# CAMERAv1_4.net
KiCad netlist of a schematic drawn in Altium Designer
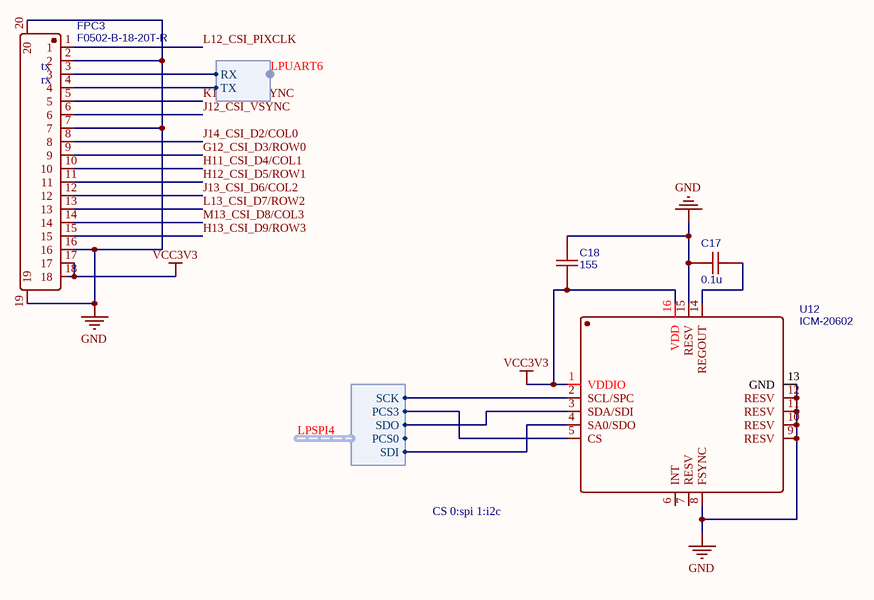
[diagram p0: CAMERAv1.4.SchDoc]

(export (version "E")
  (design (tool "Eeschema 10.0.6"))
  (components
    (comp (ref "C17")
      (value "0.1u")
      (footprint "C0603")
      (fields (field (name "CONTRIBUTOR") "LCEDA_Lib"))
      (libsource (lib "JLC") (part "C0603"))
    )
    (comp (ref "C18")
      (value "155")
      (footprint "C0603")
      (fields (field (name "CONTRIBUTOR") "LCEDA_Lib"))
      (libsource (lib "JLC") (part "C0603"))
    )
    (comp (ref "FPC3")
      (value "F0502-B-18-20T-R")
      (footprint "FPC-SMD_18P-P0.50_F0502-B-18-20T-R")
      (fields (field (name "BOM_SUPPLIER PART") "C512918") (field (name "CONTRIBUTOR") "LCSC"))
      (libsource (lib "JLC") (part "F0502-B-18-20T-R"))
    )
    (comp (ref "U12")
      (value "ICM-20602")
      (footprint "LGA-16_L3.0-W3.0-P0.50-BL")
      (fields (field (name "BOM_SUPPLIER PART") "C97633") (field (name "CONTRIBUTOR") "LCSC"))
      (libsource (lib "JLC") (part "ICM-20602"))
    )
  )
  (nets
    (net (code "2") (name "/G12_CSI_D3{slash}ROW0") (class "Default")
      (node (ref "FPC3") (pin "9") (pinfunction "9_9") (pintype "passive"))
    )
    (net (code "3") (name "/H11_CSI_D4{slash}COL1") (class "Default")
      (node (ref "FPC3") (pin "10") (pinfunction "10_10") (pintype "passive"))
    )
    (net (code "4") (name "/H12_CSI_D5{slash}ROW1") (class "Default")
      (node (ref "FPC3") (pin "11") (pinfunction "11_11") (pintype "passive"))
    )
    (net (code "5") (name "/H13_CSI_D9{slash}ROW3") (class "Default")
      (node (ref "FPC3") (pin "15") (pinfunction "15_15") (pintype "passive"))
    )
    (net (code "6") (name "/J12_CSI_VSYNC") (class "Default")
      (node (ref "FPC3") (pin "6") (pinfunction "6_6") (pintype "passive"))
    )
    (net (code "7") (name "/J13_CSI_D6{slash}COL2") (class "Default")
      (node (ref "FPC3") (pin "12") (pinfunction "12_12") (pintype "passive"))
    )
    (net (code "8") (name "/J14_CSI_D2{slash}COL0") (class "Default")
      (node (ref "FPC3") (pin "8") (pinfunction "8_8") (pintype "passive"))
    )
    (net (code "9") (name "/K10_CSI_HSYNC") (class "Default")
      (node (ref "FPC3") (pin "5") (pinfunction "5_5") (pintype "passive"))
    )
    (net (code "10") (name "/L12_CSI_PIXCLK") (class "Default")
      (node (ref "FPC3") (pin "1") (pinfunction "1_1") (pintype "passive"))
    )
    (net (code "11") (name "/L13_CSI_D7{slash}ROW2") (class "Default")
      (node (ref "FPC3") (pin "13") (pinfunction "13_13") (pintype "passive"))
    )
    (net (code "14") (name "/M13_CSI_D8{slash}COL3") (class "Default")
      (node (ref "FPC3") (pin "14") (pinfunction "14_14") (pintype "passive"))
    )
    (net (code "15") (name "/PCS3") (class "Default")
      (node (ref "U12") (pin "5") (pinfunction "CS_5") (pintype "passive"))
    )
    (net (code "16") (name "/RX") (class "Default")
      (node (ref "FPC3") (pin "3") (pinfunction "3_3") (pintype "passive"))
    )
    (net (code "17") (name "/SCK") (class "Default")
      (node (ref "U12") (pin "2") (pinfunction "SCL/SPC_2") (pintype "passive"))
    )
    (net (code "18") (name "/SDI") (class "Default")
      (node (ref "U12") (pin "4") (pinfunction "SA0/SDO_4") (pintype "passive"))
    )
    (net (code "19") (name "/SDO") (class "Default")
      (node (ref "U12") (pin "3") (pinfunction "SDA/SDI_3") (pintype "passive"))
    )
    (net (code "20") (name "/TX") (class "Default")
      (node (ref "FPC3") (pin "4") (pinfunction "4_4") (pintype "passive"))
    )
    (net (code "21") (name "GND") (class "Default")
      (node (ref "C17") (pin "1") (pinfunction "1_1") (pintype "passive"))
      (node (ref "C18") (pin "2") (pinfunction "2_2") (pintype "passive"))
      (node (ref "FPC3") (pin "16") (pinfunction "16_16") (pintype "passive"))
      (node (ref "FPC3") (pin "19") (pinfunction "19_19") (pintype "passive"))
      (node (ref "FPC3") (pin "2") (pinfunction "2_2") (pintype "passive"))
      (node (ref "FPC3") (pin "20") (pinfunction "20_20") (pintype "passive"))
      (node (ref "FPC3") (pin "7") (pinfunction "7_7") (pintype "passive"))
      (node (ref "U12") (pin "10") (pinfunction "RESV_10") (pintype "passive"))
      (node (ref "U12") (pin "11") (pinfunction "RESV_11") (pintype "passive"))
      (node (ref "U12") (pin "12") (pinfunction "RESV_12") (pintype "passive"))
      (node (ref "U12") (pin "13") (pinfunction "GND_13") (pintype "passive"))
      (node (ref "U12") (pin "15") (pinfunction "RESV_15") (pintype "passive"))
      (node (ref "U12") (pin "8") (pinfunction "FSYNC_8") (pintype "passive"))
      (node (ref "U12") (pin "9") (pinfunction "RESV_9") (pintype "passive"))
    )
    (net (code "22") (name "Net-(U12-REGOUT)") (class "Default")
      (node (ref "C17") (pin "2") (pinfunction "2_2") (pintype "passive"))
      (node (ref "U12") (pin "14") (pinfunction "REGOUT_14") (pintype "passive"))
    )
    (net (code "23") (name "VCC3V3") (class "Default")
      (node (ref "C18") (pin "1") (pinfunction "1_1") (pintype "passive"))
      (node (ref "FPC3") (pin "17") (pinfunction "17_17") (pintype "passive"))
      (node (ref "FPC3") (pin "18") (pinfunction "18_18") (pintype "passive"))
      (node (ref "U12") (pin "1") (pinfunction "VDDIO_1") (pintype "passive"))
      (node (ref "U12") (pin "16") (pinfunction "VDD_16") (pintype "passive"))
    )
    (net (code "24") (name "unconnected-(U12-INT-Pad6)") (class "Default")
      (node (ref "U12") (pin "6") (pinfunction "INT_6") (pintype "passive"))
    )
    (net (code "25") (name "unconnected-(U12-RESV-Pad7)") (class "Default")
      (node (ref "U12") (pin "7") (pinfunction "RESV_7") (pintype "passive"))
    )
  )
)
